# Sensor_Board.net
KiCad netlist of a schematic drawn in Altium Designer
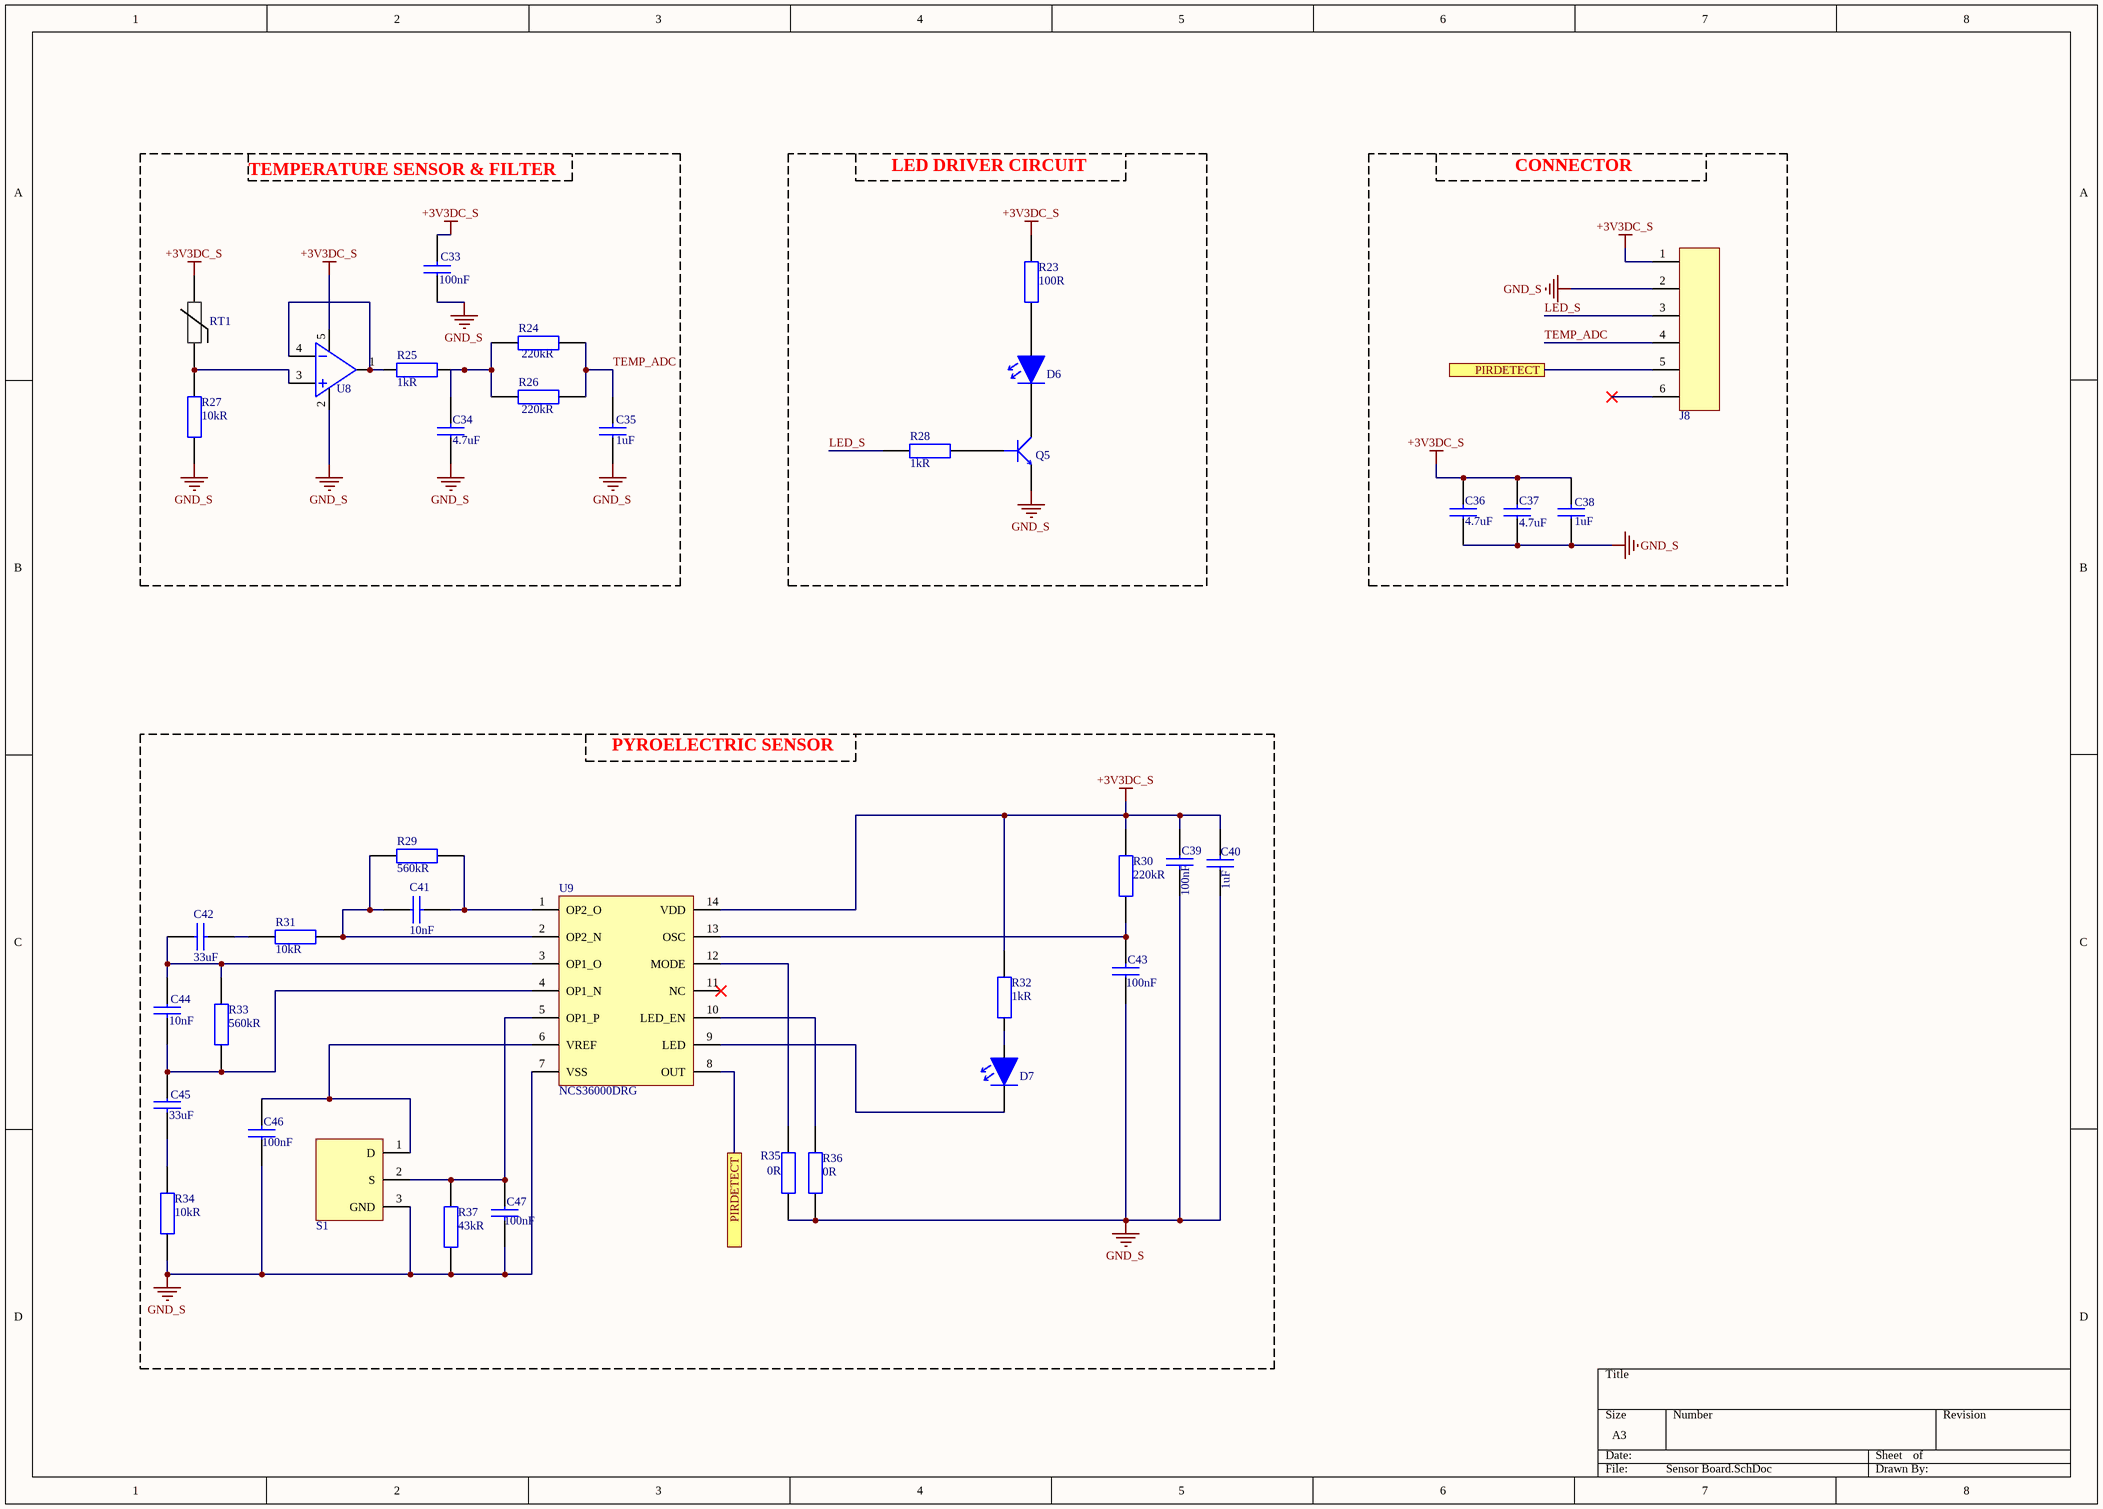
[diagram p0: Sensor Board.SchDoc]

(export (version "E")
  (design (tool "Eeschema 10.0.6"))
  (components
    (comp (ref "C33")
      (value "C0603C104K5RACTU")
      (footprint "CAP_0603")
      (description "CAP CER 100nF %10 0603 SMD")
      (fields
        (field (name "MANUFACTURER") "KEMET")
        (field (name "TOLERANCE") "10%")
        (field (name "CAPACITANCE") "100nF")
        (field (name "DESIGNED BY") "BERK")
      )
      (libsource (lib "UDEMY_Library") (part "CAP CER 100nF 0603"))
    )
    (comp (ref "C34")
      (value "CL21A475KAQNNNE")
      (footprint "CAP_0805")
      (description "CAP CER 4.7uF %10 0805")
      (fields
        (field (name "MANUFACTURER") "Samsung")
        (field (name "TOLERANCE") "10%")
        (field (name "CAPACITANCE") "4.7uF")
        (field (name "DESIGNED BY") "BERK")
      )
      (libsource (lib "UDEMY_Library") (part "CAP CER 4.7uF 0805"))
    )
    (comp (ref "C35")
      (value "CL21B105KBFNNNE")
      (footprint "CAP_0805")
      (description "CAP CER 1uF %10 0805")
      (fields
        (field (name "MANUFACTURER") "Samsung")
        (field (name "TOLERANCE") "10%")
        (field (name "CAPACITANCE") "1uF")
        (field (name "DESIGNED BY") "BERK")
      )
      (libsource (lib "UDEMY_Library") (part "CAP CER 1uF 0805"))
    )
    (comp (ref "C36")
      (value "CL21A475KAQNNNE")
      (footprint "CAP_0805")
      (description "CAP CER 4.7uF %10 0805")
      (fields
        (field (name "MANUFACTURER") "Samsung")
        (field (name "TOLERANCE") "10%")
        (field (name "CAPACITANCE") "4.7uF")
        (field (name "DESIGNED BY") "BERK")
      )
      (libsource (lib "UDEMY_Library") (part "CAP CER 4.7uF 0805"))
    )
    (comp (ref "C37")
      (value "CL21A475KAQNNNE")
      (footprint "CAP_0805")
      (description "CAP CER 4.7uF %10 0805")
      (fields
        (field (name "MANUFACTURER") "Samsung")
        (field (name "TOLERANCE") "10%")
        (field (name "CAPACITANCE") "4.7uF")
        (field (name "DESIGNED BY") "BERK")
      )
      (libsource (lib "UDEMY_Library") (part "CAP CER 4.7uF 0805"))
    )
    (comp (ref "C38")
      (value "CL21B105KBFNNNE")
      (footprint "CAP_0805")
      (description "CAP CER 1uF %10 0805")
      (fields
        (field (name "MANUFACTURER") "Samsung")
        (field (name "TOLERANCE") "10%")
        (field (name "CAPACITANCE") "1uF")
        (field (name "DESIGNED BY") "BERK")
      )
      (libsource (lib "UDEMY_Library") (part "CAP CER 1uF 0805"))
    )
    (comp (ref "C39")
      (value "C0603C104K5RACTU")
      (footprint "CAP_0603")
      (description "CAP CER 100nF %10 0603 SMD")
      (fields
        (field (name "MANUFACTURER") "KEMET")
        (field (name "TOLERANCE") "10%")
        (field (name "CAPACITANCE") "100nF")
        (field (name "DESIGNED BY") "BERK")
      )
      (libsource (lib "UDEMY_Library") (part "CAP CER 100nF 0603"))
    )
    (comp (ref "C40")
      (value "CL21B105KBFNNNE")
      (footprint "CAP_0805")
      (description "CAP CER 1uF %10 0805")
      (fields
        (field (name "MANUFACTURER") "Samsung")
        (field (name "TOLERANCE") "10%")
        (field (name "CAPACITANCE") "1uF")
        (field (name "DESIGNED BY") "BERK")
      )
      (libsource (lib "UDEMY_Library") (part "CAP CER 1uF 0805"))
    )
    (comp (ref "C41")
      (value "0603B103K160CT")
      (footprint "CAP_0603")
      (description "CAP CER 10nF %10 0603")
      (fields
        (field (name "MANUFACTURER") "Walsin Technologies")
        (field (name "TOLERANCE") "10%")
        (field (name "CAPACITANCE") "10nF")
        (field (name "DESIGNED BY") "BERK")
      )
      (libsource (lib "UDEMY_Library") (part "CAP CER 10nF 0603"))
    )
    (comp (ref "C42")
      (value "C3216X5R1E336M160AC")
      (footprint "CAP_1206")
      (description "CAP CER 33uF %20 1206 SMD")
      (fields
        (field (name "MANUFACTURER") "TDK")
        (field (name "TOLERANCE") "20%")
        (field (name "CAPACITANCE") "33uF")
        (field (name "DESIGNED BY") "BERK")
      )
      (libsource (lib "UDEMY_Library") (part "CAP CER 33uF 1206"))
    )
    (comp (ref "C43")
      (value "C0603C104K5RACTU")
      (footprint "CAP_0603")
      (description "CAP CER 100nF %10 0603 SMD")
      (fields
        (field (name "MANUFACTURER") "KEMET")
        (field (name "TOLERANCE") "10%")
        (field (name "CAPACITANCE") "100nF")
        (field (name "DESIGNED BY") "BERK")
      )
      (libsource (lib "UDEMY_Library") (part "CAP CER 100nF 0603"))
    )
    (comp (ref "C44")
      (value "0603B103K160CT")
      (footprint "CAP_0603")
      (description "CAP CER 10nF %10 0603")
      (fields
        (field (name "MANUFACTURER") "Walsin Technologies")
        (field (name "TOLERANCE") "10%")
        (field (name "CAPACITANCE") "10nF")
        (field (name "DESIGNED BY") "BERK")
      )
      (libsource (lib "UDEMY_Library") (part "CAP CER 10nF 0603"))
    )
    (comp (ref "C45")
      (value "C3216X5R1E336M160AC")
      (footprint "CAP_1206")
      (description "CAP CER 33uF %20 1206 SMD")
      (fields
        (field (name "MANUFACTURER") "TDK")
        (field (name "TOLERANCE") "20%")
        (field (name "CAPACITANCE") "33uF")
        (field (name "DESIGNED BY") "BERK")
      )
      (libsource (lib "UDEMY_Library") (part "CAP CER 33uF 1206"))
    )
    (comp (ref "C46")
      (value "C0603C104K5RACTU")
      (footprint "CAP_0603")
      (description "CAP CER 100nF %10 0603 SMD")
      (fields
        (field (name "MANUFACTURER") "KEMET")
        (field (name "TOLERANCE") "10%")
        (field (name "CAPACITANCE") "100nF")
        (field (name "DESIGNED BY") "BERK")
      )
      (libsource (lib "UDEMY_Library") (part "CAP CER 100nF 0603"))
    )
    (comp (ref "C47")
      (value "C0603C104K5RACTU")
      (footprint "CAP_0603")
      (description "CAP CER 100nF %10 0603 SMD")
      (fields
        (field (name "MANUFACTURER") "KEMET")
        (field (name "TOLERANCE") "10%")
        (field (name "CAPACITANCE") "100nF")
        (field (name "DESIGNED BY") "BERK")
      )
      (libsource (lib "UDEMY_Library") (part "CAP CER 100nF 0603"))
    )
    (comp (ref "D6")
      (value "LH R974-LP-1")
      (footprint "LED_RED_0805")
      (description "LED Uni-Color Hyper Red 660nm 2-Pin Chip 0805(2012Metric) T/R")
      (fields (field (name "MANUFACTURER") "Osram Opto") (field (name "DESIGNED BY") "BERK"))
      (libsource (lib "UDEMY_Library") (part "LED RED 0805"))
    )
    (comp (ref "D7")
      (value "LTST-C171GKT")
      (footprint "LED_GREEN_0805")
      (description "Green 0805 130 º Min 5 mcd Typical 12 mcd Water Clear Lens SMT LED")
      (fields (field (name "MANUFACTURER") "Vishay Lite-On") (field (name "DESIGNED BY") "BERK"))
      (libsource (lib "UDEMY_Library") (part "LED GREEN 0805"))
    )
    (comp (ref "J8")
      (value "64800611622")
      (footprint "64800611622")
      (description "1.50mm 6PIN Connector")
      (fields (field (name "MANUFACTURER") "Wurth Electronics"))
      (libsource (lib "UDEMY_Library") (part "64800611622_conn_6pin"))
    )
    (comp (ref "Q5")
      (value "MMBT3904-7-F")
      (footprint "SOT-23F")
      (description "Transistor General Purpose BJT NPN 40 Volt 0.2A Automotive 3-Pin SOT-23")
      (fields (field (name "MANUFACTURER") "Diodes Zetex") (field (name "DESIGNED BY") "BERK"))
      (libsource (lib "UDEMY_Library") (part "MMBT3904-7-F"))
    )
    (comp (ref "R23")
      (value "RC0603JR-07100RL")
      (footprint "RES_0603")
      (description "RES 100 %5 OHM 0603 SMD")
      (fields
        (field (name "MANUFACTURER") "Yageo")
        (field (name "TOLERANCE") "5%")
        (field (name "RESISTANCE") "100R")
        (field (name "DESIGNED BY") "BERK")
      )
      (libsource (lib "UDEMY_Library") (part "RES 100 OHM 0603"))
    )
    (comp (ref "R24")
      (value "RC0603JR-07220KL")
      (footprint "RES_0603")
      (description "RES 220K %5 OHM 0603 SMD")
      (fields
        (field (name "MANUFACTURER") "Yageo")
        (field (name "TOLERANCE") "5%")
        (field (name "RESISTANCE") "220kR")
      )
      (libsource (lib "UDEMY_Library") (part "RES 220K OHM 0603"))
    )
    (comp (ref "R25")
      (value "RC0603FR-0710KL")
      (footprint "RES_0603")
      (description "RES 1K %1 OHM 0603 SMD")
      (fields
        (field (name "MANUFACTURER") "Yageo")
        (field (name "MANUFACTURER PART NUMBER") "RC0603JR-071KL")
        (field (name "RESISTANCE") "1kR")
        (field (name "DESIGNED BY") "BERK")
      )
      (libsource (lib "UDEMY_Library") (part "RES 1K OHM 0603"))
    )
    (comp (ref "R26")
      (value "RC0603JR-07220KL")
      (footprint "RES_0603")
      (description "RES 220K %5 OHM 0603 SMD")
      (fields
        (field (name "MANUFACTURER") "Yageo")
        (field (name "TOLERANCE") "5%")
        (field (name "RESISTANCE") "220kR")
      )
      (libsource (lib "UDEMY_Library") (part "RES 220K OHM 0603"))
    )
    (comp (ref "R27")
      (value "RC0603FR-0710KL")
      (footprint "RES_0603")
      (description "RES 10K %1 OHM 0603 SMD")
      (fields
        (field (name "MANUFACTURER") "Yageo")
        (field (name "TOLERANCE") "1%")
        (field (name "RESISTANCE") "10kR")
        (field (name "DESIGNED BY") "BERK")
      )
      (libsource (lib "UDEMY_Library") (part "RES 10K OHM 0603"))
    )
    (comp (ref "R28")
      (value "RC0603FR-0710KL")
      (footprint "RES_0603")
      (description "RES 1K %1 OHM 0603 SMD")
      (fields
        (field (name "MANUFACTURER") "Yageo")
        (field (name "MANUFACTURER PART NUMBER") "RC0603JR-071KL")
        (field (name "RESISTANCE") "1kR")
        (field (name "DESIGNED BY") "BERK")
      )
      (libsource (lib "UDEMY_Library") (part "RES 1K OHM 0603"))
    )
    (comp (ref "R29")
      (value "RC0603JR-07560KL")
      (footprint "RES_0603")
      (description "RES SMD 560K OHM 5% 1/10W 0603")
      (fields
        (field (name "MANUFACTURER") "Yageo")
        (field (name "TOLERANCE") "5%")
        (field (name "RESISTANCE") "560kR")
        (field (name "DESIGNED BY") "BERK")
      )
      (libsource (lib "") (part "RES 560K OHM 0603_1"))
    )
    (comp (ref "R30")
      (value "RC0603JR-07220KL")
      (footprint "RES_0603")
      (description "RES 220K %5 OHM 0603 SMD")
      (fields
        (field (name "MANUFACTURER") "Yageo")
        (field (name "TOLERANCE") "5%")
        (field (name "RESISTANCE") "220kR")
      )
      (libsource (lib "") (part "RES 220K OHM 0603_1"))
    )
    (comp (ref "R31")
      (value "RC0603FR-0710KL")
      (footprint "RES_0603")
      (description "RES 10K %1 OHM 0603 SMD")
      (fields
        (field (name "MANUFACTURER") "Yageo")
        (field (name "TOLERANCE") "1%")
        (field (name "RESISTANCE") "10kR")
        (field (name "DESIGNED BY") "BERK")
      )
      (libsource (lib "") (part "RES 10K OHM 0603_2"))
    )
    (comp (ref "R32")
      (value "RC0603FR-0710KL")
      (footprint "RES_0603")
      (description "RES 1K %1 OHM 0603 SMD")
      (fields
        (field (name "MANUFACTURER") "Yageo")
        (field (name "MANUFACTURER PART NUMBER") "RC0603JR-071KL")
        (field (name "RESISTANCE") "1kR")
        (field (name "DESIGNED BY") "BERK")
      )
      (libsource (lib "") (part "RES 1K OHM 0603_1"))
    )
    (comp (ref "R33")
      (value "RC0603JR-07560KL")
      (footprint "RES_0603")
      (description "RES SMD 560K OHM 5% 1/10W 0603")
      (fields
        (field (name "MANUFACTURER") "Yageo")
        (field (name "TOLERANCE") "5%")
        (field (name "RESISTANCE") "560kR")
        (field (name "DESIGNED BY") "BERK")
      )
      (libsource (lib "UDEMY_Library") (part "RES 560K OHM 0603"))
    )
    (comp (ref "R34")
      (value "RC0603FR-0710KL")
      (footprint "RES_0603")
      (description "RES 10K %1 OHM 0603 SMD")
      (fields
        (field (name "MANUFACTURER") "Yageo")
        (field (name "TOLERANCE") "1%")
        (field (name "RESISTANCE") "10kR")
        (field (name "DESIGNED BY") "BERK")
      )
      (libsource (lib "") (part "RES 10K OHM 0603_1"))
    )
    (comp (ref "R35")
      (value "RC0603JR-070RL")
      (footprint "RES_0603")
      (description "RES 0 %1 OHM 0603 SMD")
      (fields
        (field (name "MANUFACTURER") "Yageo")
        (field (name "TOLERANCE") "1%")
        (field (name "RESISTANCE") "0R")
        (field (name "DESIGNED BY") "BERK")
      )
      (libsource (lib "UDEMY_Library") (part "RES 0 OHM 0603"))
    )
    (comp (ref "R36")
      (value "RC0603JR-070RL")
      (footprint "RES_0603")
      (description "RES 0 %1 OHM 0603 SMD")
      (fields
        (field (name "MANUFACTURER") "Yageo")
        (field (name "TOLERANCE") "1%")
        (field (name "RESISTANCE") "0R")
        (field (name "DESIGNED BY") "BERK")
      )
      (libsource (lib "UDEMY_Library") (part "RES 0 OHM 0603"))
    )
    (comp (ref "R37")
      (value "RC0603JR-0743KL")
      (footprint "RES_0603")
      (description "RES 43K %5 OHM 0603 SMD")
      (fields
        (field (name "MANUFACTURER") "Yageo")
        (field (name "TOLERANCE") "5%")
        (field (name "RESISTANCE") "43kR")
        (field (name "DESIGNED BY") "BERK")
      )
      (libsource (lib "UDEMY_Library") (part "RES 43K OHM 0603"))
    )
    (comp (ref "RT1")
      (value "TFPT1206L1002FM")
      (footprint "RES_1206")
      (description "Thermistor PTC 10K Ohm 1% 1206")
      (fields
        (field (name "MANUFACTURER") "Vishay Dale")
        (field (name "TOLERANCE") "1%")
        (field (name "DESIGNED BY") "BERK")
      )
      (libsource (lib "UDEMY_Library") (part "TFPT1206L1002FM"))
    )
    (comp (ref "S1")
      (value "LHI 878/3902")
      (footprint "LHI 878")
      (description "SENSOR PYRO DETECTOR DUAL MOTION")
      (fields (field (name "DESIGNED BY") "BERK"))
      (libsource (lib "UDEMY_Library") (part "LHI 878/3902"))
    )
    (comp (ref "U8")
      (value "OPA314AIDBVR")
      (footprint "SOT23-5")
      (description "Op Amp OPA314")
      (fields (field (name "MANUFACTURER") "Texas Instruments") (field (name "DESIGNED BY") "BERK"))
      (libsource (lib "UDEMY_Library") (part "OPA314"))
    )
    (comp (ref "U9")
      (value "NCS36000DRG")
      (footprint "SOIC14")
      (description "PIR Controller Low Noise Amplifiers and LDO Regulator 14-Pin SOIC N T/R")
      (fields (field (name "MANUFACTURER") "ON Semiconductor") (field (name "DESIGNED BY") "BERK"))
      (libsource (lib "UDEMY_Library") (part "NCS36000"))
    )
  )
  (nets
    (net (code "1") (name "+3V3DC_S") (class "Default")
      (node (ref "C33") (pin "2") (pinfunction "2_2") (pintype "passive"))
      (node (ref "C36") (pin "2") (pinfunction "2_2") (pintype "passive"))
      (node (ref "C37") (pin "2") (pinfunction "2_2") (pintype "passive"))
      (node (ref "C38") (pin "2") (pinfunction "2_2") (pintype "passive"))
      (node (ref "C39") (pin "1") (pinfunction "1_1") (pintype "passive"))
      (node (ref "C40") (pin "2") (pinfunction "2_2") (pintype "passive"))
      (node (ref "J8") (pin "1") (pintype "power_in"))
      (node (ref "R23") (pin "2") (pinfunction "2_2") (pintype "passive"))
      (node (ref "R30") (pin "2") (pinfunction "2_2") (pintype "passive"))
      (node (ref "R32") (pin "2") (pinfunction "2_2") (pintype "passive"))
      (node (ref "RT1") (pin "2") (pinfunction "2_2") (pintype "passive"))
      (node (ref "U8") (pin "5") (pinfunction "5_5") (pintype "passive"))
      (node (ref "U9") (pin "14") (pinfunction "VDD_14") (pintype "passive"))
    )
    (net (code "2") (name "/LED_S") (class "Default")
      (node (ref "J8") (pin "3") (pintype "power_in"))
      (node (ref "R28") (pin "1") (pinfunction "1_1") (pintype "passive"))
    )
    (net (code "3") (name "/PIRDETECT") (class "Default")
      (node (ref "J8") (pin "5") (pintype "power_in"))
      (node (ref "U9") (pin "8") (pinfunction "OUT_8") (pintype "passive"))
    )
    (net (code "4") (name "/TEMP_ADC") (class "Default")
      (node (ref "C35") (pin "2") (pinfunction "2_2") (pintype "passive"))
      (node (ref "J8") (pin "4") (pintype "power_in"))
      (node (ref "R24") (pin "2") (pinfunction "2_2") (pintype "passive"))
      (node (ref "R26") (pin "2") (pinfunction "2_2") (pintype "passive"))
    )
    (net (code "5") (name "GND_S") (class "Default")
      (node (ref "C33") (pin "1") (pinfunction "1_1") (pintype "passive"))
      (node (ref "C34") (pin "1") (pinfunction "1_1") (pintype "passive"))
      (node (ref "C35") (pin "1") (pinfunction "1_1") (pintype "passive"))
      (node (ref "C36") (pin "1") (pinfunction "1_1") (pintype "passive"))
      (node (ref "C37") (pin "1") (pinfunction "1_1") (pintype "passive"))
      (node (ref "C38") (pin "1") (pinfunction "1_1") (pintype "passive"))
      (node (ref "C39") (pin "2") (pinfunction "2_2") (pintype "passive"))
      (node (ref "C40") (pin "1") (pinfunction "1_1") (pintype "passive"))
      (node (ref "C43") (pin "1") (pinfunction "1_1") (pintype "passive"))
      (node (ref "C46") (pin "1") (pinfunction "1_1") (pintype "passive"))
      (node (ref "C47") (pin "2") (pinfunction "2_2") (pintype "passive"))
      (node (ref "J8") (pin "2") (pintype "power_in"))
      (node (ref "Q5") (pin "2") (pinfunction "E_2") (pintype "power_in"))
      (node (ref "R27") (pin "1") (pinfunction "1_1") (pintype "passive"))
      (node (ref "R34") (pin "2") (pinfunction "2_2") (pintype "passive"))
      (node (ref "R35") (pin "1") (pinfunction "1_1") (pintype "passive"))
      (node (ref "R36") (pin "1") (pinfunction "1_1") (pintype "passive"))
      (node (ref "R37") (pin "1") (pinfunction "1_1") (pintype "passive"))
      (node (ref "S1") (pin "3") (pinfunction "GND_3") (pintype "passive"))
      (node (ref "U8") (pin "2") (pinfunction "2_2") (pintype "passive"))
      (node (ref "U9") (pin "7") (pinfunction "VSS_7") (pintype "passive"))
    )
    (net (code "6") (name "Net-(C34-Pad2)") (class "Default")
      (node (ref "C34") (pin "2") (pinfunction "2_2") (pintype "passive"))
      (node (ref "R24") (pin "1") (pinfunction "1_1") (pintype "passive"))
      (node (ref "R25") (pin "2") (pinfunction "2_2") (pintype "passive"))
      (node (ref "R26") (pin "1") (pinfunction "1_1") (pintype "passive"))
    )
    (net (code "7") (name "Net-(C42-Pad2)") (class "Default")
      (node (ref "C42") (pin "2") (pinfunction "2_2") (pintype "passive"))
      (node (ref "R31") (pin "1") (pinfunction "1_1") (pintype "passive"))
    )
    (net (code "8") (name "Net-(C45-Pad2)") (class "Default")
      (node (ref "C45") (pin "2") (pinfunction "2_2") (pintype "passive"))
      (node (ref "R34") (pin "1") (pinfunction "1_1") (pintype "passive"))
    )
    (net (code "9") (name "Net-(D6-Pad2)") (class "Default")
      (node (ref "D6") (pin "2") (pinfunction "2_2") (pintype "power_in"))
      (node (ref "R23") (pin "1") (pinfunction "1_1") (pintype "passive"))
    )
    (net (code "10") (name "Net-(D7-Pad2)") (class "Default")
      (node (ref "D7") (pin "2") (pinfunction "2_2") (pintype "power_in"))
      (node (ref "R32") (pin "1") (pinfunction "1_1") (pintype "passive"))
    )
    (net (code "11") (name "Net-(Q5-B)") (class "Default")
      (node (ref "Q5") (pin "1") (pinfunction "B_1") (pintype "power_in"))
      (node (ref "R28") (pin "2") (pinfunction "2_2") (pintype "passive"))
    )
    (net (code "12") (name "Net-(Q5-C)") (class "Default")
      (node (ref "D6") (pin "1") (pinfunction "1_1") (pintype "power_in"))
      (node (ref "Q5") (pin "3") (pinfunction "C_3") (pintype "power_in"))
    )
    (net (code "13") (name "Net-(R25-Pad1)") (class "Default")
      (node (ref "R25") (pin "1") (pinfunction "1_1") (pintype "passive"))
      (node (ref "U8") (pin "1") (pinfunction "1_1") (pintype "passive"))
      (node (ref "U8") (pin "4") (pinfunction "4_4") (pintype "passive"))
    )
    (net (code "14") (name "Net-(R27-Pad2)") (class "Default")
      (node (ref "R27") (pin "2") (pinfunction "2_2") (pintype "passive"))
      (node (ref "RT1") (pin "1") (pinfunction "1_1") (pintype "passive"))
      (node (ref "U8") (pin "3") (pinfunction "3_3") (pintype "passive"))
    )
    (net (code "15") (name "Net-(S1-D)") (class "Default")
      (node (ref "C46") (pin "2") (pinfunction "2_2") (pintype "passive"))
      (node (ref "S1") (pin "1") (pinfunction "D_1") (pintype "passive"))
      (node (ref "U9") (pin "6") (pinfunction "VREF_6") (pintype "passive"))
    )
    (net (code "16") (name "Net-(S1-S)") (class "Default")
      (node (ref "C47") (pin "1") (pinfunction "1_1") (pintype "passive"))
      (node (ref "R37") (pin "2") (pinfunction "2_2") (pintype "passive"))
      (node (ref "S1") (pin "2") (pinfunction "S_2") (pintype "passive"))
      (node (ref "U9") (pin "5") (pinfunction "OP1_P_5") (pintype "passive"))
    )
    (net (code "17") (name "Net-(U9-LED)") (class "Default")
      (node (ref "D7") (pin "1") (pinfunction "1_1") (pintype "power_in"))
      (node (ref "U9") (pin "9") (pinfunction "LED_9") (pintype "passive"))
    )
    (net (code "18") (name "Net-(U9-LED_EN)") (class "Default")
      (node (ref "R36") (pin "2") (pinfunction "2_2") (pintype "passive"))
      (node (ref "U9") (pin "10") (pinfunction "LED_EN_10") (pintype "passive"))
    )
    (net (code "19") (name "Net-(U9-MODE)") (class "Default")
      (node (ref "R35") (pin "2") (pinfunction "2_2") (pintype "passive"))
      (node (ref "U9") (pin "12") (pinfunction "MODE_12") (pintype "passive"))
    )
    (net (code "20") (name "Net-(U9-OP1_N)") (class "Default")
      (node (ref "C44") (pin "2") (pinfunction "2_2") (pintype "passive"))
      (node (ref "C45") (pin "1") (pinfunction "1_1") (pintype "passive"))
      (node (ref "R33") (pin "2") (pinfunction "2_2") (pintype "passive"))
      (node (ref "U9") (pin "4") (pinfunction "OP1_N_4") (pintype "passive"))
    )
    (net (code "21") (name "Net-(U9-OP1_O)") (class "Default")
      (node (ref "C42") (pin "1") (pinfunction "1_1") (pintype "passive"))
      (node (ref "C44") (pin "1") (pinfunction "1_1") (pintype "passive"))
      (node (ref "R33") (pin "1") (pinfunction "1_1") (pintype "passive"))
      (node (ref "U9") (pin "3") (pinfunction "OP1_O_3") (pintype "passive"))
    )
    (net (code "22") (name "Net-(U9-OP2_N)") (class "Default")
      (node (ref "C41") (pin "1") (pinfunction "1_1") (pintype "passive"))
      (node (ref "R29") (pin "1") (pinfunction "1_1") (pintype "passive"))
      (node (ref "R31") (pin "2") (pinfunction "2_2") (pintype "passive"))
      (node (ref "U9") (pin "2") (pinfunction "OP2_N_2") (pintype "passive"))
    )
    (net (code "23") (name "Net-(U9-OP2_O)") (class "Default")
      (node (ref "C41") (pin "2") (pinfunction "2_2") (pintype "passive"))
      (node (ref "R29") (pin "2") (pinfunction "2_2") (pintype "passive"))
      (node (ref "U9") (pin "1") (pinfunction "OP2_O_1") (pintype "passive"))
    )
    (net (code "24") (name "Net-(U9-OSC)") (class "Default")
      (node (ref "C43") (pin "2") (pinfunction "2_2") (pintype "passive"))
      (node (ref "R30") (pin "1") (pinfunction "1_1") (pintype "passive"))
      (node (ref "U9") (pin "13") (pinfunction "OSC_13") (pintype "passive"))
    )
    (net (code "25") (name "unconnected-(J8-Pad6)") (class "Default")
      (node (ref "J8") (pin "6") (pintype "power_in+no_connect"))
    )
    (net (code "26") (name "unconnected-(U9-NC-Pad11)") (class "Default")
      (node (ref "U9") (pin "11") (pinfunction "NC_11") (pintype "passive+no_connect"))
    )
  )
)
